# DC26_HHV_challenge.net
KiCad netlist of a schematic drawn in EAGLE
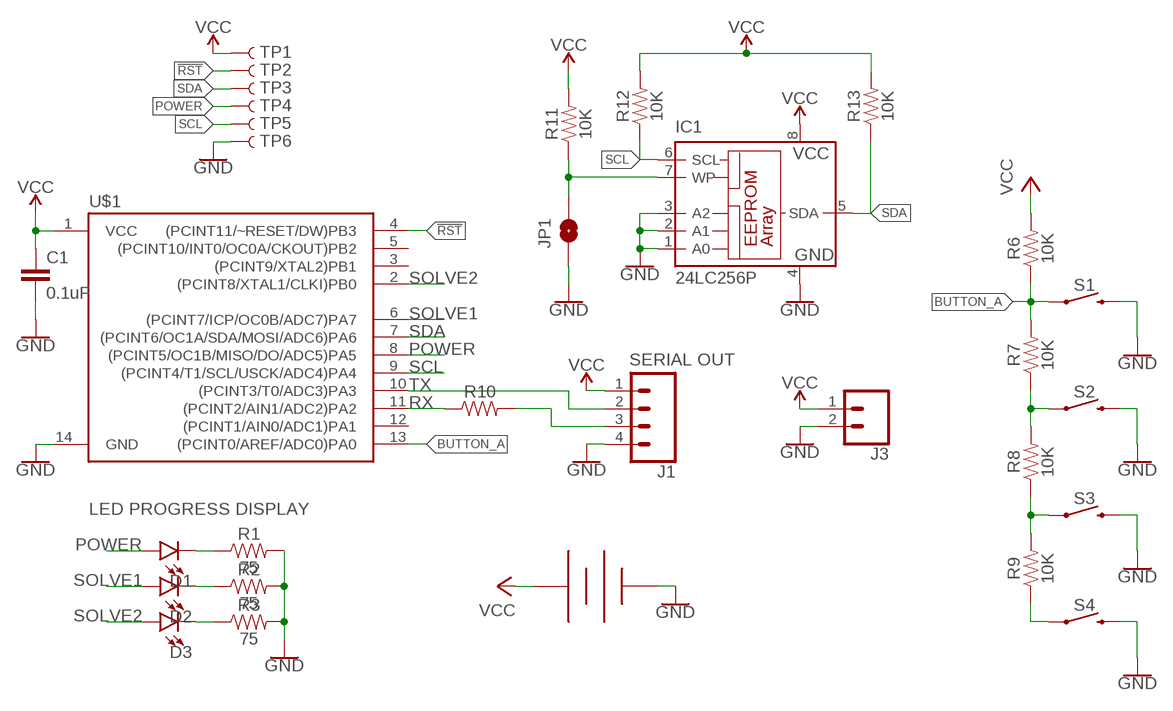
[diagram p0: schematic, sheet 1]

(export (version "E")
  (design (tool "Eeschema 10.0.6"))
  (components
    (comp (ref "BT1")
      (value "BAT-HLD-001-THM")
      (footprint "eagle-import:BAT-HLD-001-THM")
      (libsource (lib "eagle-import") (part "BAT-HLD-001-THM"))
    )
    (comp (ref "C1")
      (value "0.1uF")
      (footprint "eagle-import:0603")
      (libsource (lib "eagle-import") (part "0.1UF-0603-25V-(+80/-20%)"))
    )
    (comp (ref "D1")
      (value "LED5MM")
      (footprint "eagle-import:LED_5MM")
      (libsource (lib "eagle-import") (part "LED5MM"))
    )
    (comp (ref "D2")
      (value "LED5MM")
      (footprint "eagle-import:LED_5MM")
      (libsource (lib "eagle-import") (part "LED5MM"))
    )
    (comp (ref "D3")
      (value "LED5MM")
      (footprint "eagle-import:LED_5MM")
      (libsource (lib "eagle-import") (part "LED5MM"))
    )
    (comp (ref "IC1")
      (value "24LC256P")
      (footprint "eagle-import:DIL8")
      (fields (field (name "MF") "MICROCHIP") (field (name "MPN") "24LC256-E/P"))
      (libsource (lib "eagle-import") (part "24PLC256"))
    )
    (comp (ref "J1")
      (value "CONN_04LOCK")
      (footprint "eagle-import:1X04_LOCK")
      (libsource (lib "eagle-import") (part "CONN_04LOCK"))
    )
    (comp (ref "J3")
      (value "CONN_02PTH3")
      (footprint "eagle-import:1X02_LONGPADS")
      (libsource (lib "eagle-import") (part "CONN_02PTH3"))
    )
    (comp (ref "JP1")
      (value "JUMPER-SMT_2_NO_SILK")
      (footprint "eagle-import:SMT-JUMPER_2_NO_SILK")
      (libsource (lib "eagle-import") (part "JUMPER-SMT_2_NO_SILK"))
    )
    (comp (ref "R1")
      (value "75")
      (footprint "eagle-import:0805")
      (libsource (lib "eagle-import") (part "RESISTOR0805"))
    )
    (comp (ref "R2")
      (value "75")
      (footprint "eagle-import:0805")
      (libsource (lib "eagle-import") (part "RESISTOR0805"))
    )
    (comp (ref "R3")
      (value "75")
      (footprint "eagle-import:0805")
      (libsource (lib "eagle-import") (part "RESISTOR0805"))
    )
    (comp (ref "R6")
      (value "10K")
      (footprint "eagle-import:AXIAL-0.3")
      (libsource (lib "eagle-import") (part "RESISTORAXIAL-0.3"))
    )
    (comp (ref "R7")
      (value "10K")
      (footprint "eagle-import:AXIAL-0.3")
      (libsource (lib "eagle-import") (part "RESISTORAXIAL-0.3"))
    )
    (comp (ref "R8")
      (value "10K")
      (footprint "eagle-import:AXIAL-0.3")
      (libsource (lib "eagle-import") (part "RESISTORAXIAL-0.3"))
    )
    (comp (ref "R9")
      (value "10K")
      (footprint "eagle-import:AXIAL-0.3")
      (libsource (lib "eagle-import") (part "RESISTORAXIAL-0.3"))
    )
    (comp (ref "R10")
      (value "RESISTOR0805")
      (footprint "eagle-import:0805")
      (libsource (lib "eagle-import") (part "RESISTOR0805"))
    )
    (comp (ref "R11")
      (value "10K")
      (footprint "eagle-import:AXIAL-0.3")
      (libsource (lib "eagle-import") (part "RESISTORAXIAL-0.3"))
    )
    (comp (ref "R12")
      (value "10K")
      (footprint "eagle-import:AXIAL-0.3")
      (libsource (lib "eagle-import") (part "RESISTORAXIAL-0.3"))
    )
    (comp (ref "R13")
      (value "10K")
      (footprint "eagle-import:AXIAL-0.3")
      (libsource (lib "eagle-import") (part "RESISTORAXIAL-0.3"))
    )
    (comp (ref "S1")
      (value "MOMENTARY-SWITCH-SPST-PTH-6.0MM")
      (footprint "eagle-import:TACTILE_SWITCH_PTH_6.0MM")
      (libsource (lib "eagle-import") (part "MOMENTARY-SWITCH-SPST-PTH-6.0MM"))
    )
    (comp (ref "S2")
      (value "MOMENTARY-SWITCH-SPST-PTH-6.0MM")
      (footprint "eagle-import:TACTILE_SWITCH_PTH_6.0MM")
      (libsource (lib "eagle-import") (part "MOMENTARY-SWITCH-SPST-PTH-6.0MM"))
    )
    (comp (ref "S3")
      (value "MOMENTARY-SWITCH-SPST-PTH-6.0MM")
      (footprint "eagle-import:TACTILE_SWITCH_PTH_6.0MM")
      (libsource (lib "eagle-import") (part "MOMENTARY-SWITCH-SPST-PTH-6.0MM"))
    )
    (comp (ref "S4")
      (value "MOMENTARY-SWITCH-SPST-PTH-6.0MM")
      (footprint "eagle-import:TACTILE_SWITCH_PTH_6.0MM")
      (libsource (lib "eagle-import") (part "MOMENTARY-SWITCH-SPST-PTH-6.0MM"))
    )
    (comp (ref "TP1")
      (value "TEST-POINT3X4")
      (footprint "eagle-import:PAD.03X.04")
      (libsource (lib "eagle-import") (part "TEST-POINT3X4"))
    )
    (comp (ref "TP2")
      (value "TEST-POINT3X4")
      (footprint "eagle-import:PAD.03X.04")
      (libsource (lib "eagle-import") (part "TEST-POINT3X4"))
    )
    (comp (ref "TP3")
      (value "TEST-POINT3X4")
      (footprint "eagle-import:PAD.03X.04")
      (libsource (lib "eagle-import") (part "TEST-POINT3X4"))
    )
    (comp (ref "TP4")
      (value "TEST-POINT3X4")
      (footprint "eagle-import:PAD.03X.04")
      (libsource (lib "eagle-import") (part "TEST-POINT3X4"))
    )
    (comp (ref "TP5")
      (value "TEST-POINT3X4")
      (footprint "eagle-import:PAD.03X.04")
      (libsource (lib "eagle-import") (part "TEST-POINT3X4"))
    )
    (comp (ref "TP6")
      (value "TEST-POINT3X4")
      (footprint "eagle-import:PAD.03X.04")
      (libsource (lib "eagle-import") (part "TEST-POINT3X4"))
    )
    (comp (ref "U$1")
      (value "ATTINY84ATTINY84-20PU")
      (footprint "eagle-import:DIP14")
      (libsource (lib "eagle-import") (part "ATTINY84ATTINY84-20PU"))
    )
  )
  (nets
    (net (code "1") (name "/RX") (class "Default")
      (node (ref "J1") (pin "3") (pinfunction "3_3") (pintype "passive"))
      (node (ref "R10") (pin "2") (pinfunction "2_2") (pintype "passive"))
    )
    (net (code "2") (name "/SOLVE1") (class "Default")
      (node (ref "D2") (pin "A") (pinfunction "A_A") (pintype "passive"))
      (node (ref "U$1") (pin "6") (pinfunction "(PCINT7/ICP/OC0B/ADC7)PA7_6") (pintype "bidirectional"))
    )
    (net (code "3") (name "/SOLVE2") (class "Default")
      (node (ref "D3") (pin "A") (pinfunction "A_A") (pintype "passive"))
      (node (ref "U$1") (pin "2") (pinfunction "(PCINT8/XTAL1/CLKI)PB0_2") (pintype "bidirectional"))
    )
    (net (code "4") (name "/TX") (class "Default")
      (node (ref "J1") (pin "2") (pinfunction "2_2") (pintype "passive"))
      (node (ref "U$1") (pin "10") (pinfunction "(PCINT3/T0/ADC3)PA3_10") (pintype "bidirectional"))
    )
    (net (code "5") (name "/~{RST}") (class "Default")
      (node (ref "TP2") (pin "P$1") (pinfunction "1_P$1") (pintype "bidirectional"))
      (node (ref "U$1") (pin "4") (pinfunction "(PCINT11/~{RESET/DW})PB3_4") (pintype "bidirectional"))
    )
    (net (code "6") (name "BUTTON_A") (class "Default")
      (node (ref "R6") (pin "P$1") (pinfunction "1_P$1") (pintype "passive"))
      (node (ref "R7") (pin "P$2") (pinfunction "2_P$2") (pintype "passive"))
      (node (ref "S1") (pin "1") (pinfunction "1_1") (pintype "passive"))
      (node (ref "U$1") (pin "13") (pinfunction "(PCINT0/AREF/ADC0)PA0_13") (pintype "bidirectional"))
    )
    (net (code "7") (name "GND") (class "Default")
      (node (ref "BT1") (pin "-") (pinfunction "VSS_-") (pintype "bidirectional"))
      (node (ref "C1") (pin "2") (pinfunction "2_2") (pintype "passive"))
      (node (ref "IC1") (pin "1") (pinfunction "A0_1") (pintype "input"))
      (node (ref "IC1") (pin "2") (pinfunction "A1_2") (pintype "input"))
      (node (ref "IC1") (pin "3") (pinfunction "A2_3") (pintype "input"))
      (node (ref "IC1") (pin "4") (pinfunction "GND_4") (pintype "power_in"))
      (node (ref "J1") (pin "4") (pinfunction "4_4") (pintype "passive"))
      (node (ref "J3") (pin "2") (pinfunction "2_2") (pintype "passive"))
      (node (ref "JP1") (pin "1") (pinfunction "1_1") (pintype "passive"))
      (node (ref "R1") (pin "2") (pinfunction "2_2") (pintype "passive"))
      (node (ref "R2") (pin "2") (pinfunction "2_2") (pintype "passive"))
      (node (ref "R3") (pin "2") (pinfunction "2_2") (pintype "passive"))
      (node (ref "S1") (pin "3") (pinfunction "2_3") (pintype "passive"))
      (node (ref "S2") (pin "3") (pinfunction "2_3") (pintype "passive"))
      (node (ref "S3") (pin "3") (pinfunction "2_3") (pintype "passive"))
      (node (ref "S4") (pin "3") (pinfunction "2_3") (pintype "passive"))
      (node (ref "TP6") (pin "P$1") (pinfunction "1_P$1") (pintype "bidirectional"))
      (node (ref "U$1") (pin "14") (pinfunction "GND_14") (pintype "bidirectional"))
    )
    (net (code "8") (name "Net-(D1-C)") (class "Default")
      (node (ref "D1") (pin "K") (pinfunction "C_K") (pintype "passive"))
      (node (ref "R1") (pin "1") (pinfunction "1_1") (pintype "passive"))
    )
    (net (code "9") (name "Net-(D2-C)") (class "Default")
      (node (ref "D2") (pin "K") (pinfunction "C_K") (pintype "passive"))
      (node (ref "R2") (pin "1") (pinfunction "1_1") (pintype "passive"))
    )
    (net (code "10") (name "Net-(D3-C)") (class "Default")
      (node (ref "D3") (pin "K") (pinfunction "C_K") (pintype "passive"))
      (node (ref "R3") (pin "1") (pinfunction "1_1") (pintype "passive"))
    )
    (net (code "11") (name "Net-(IC1-WP)") (class "Default")
      (node (ref "IC1") (pin "7") (pinfunction "WP_7") (pintype "input"))
      (node (ref "JP1") (pin "2") (pinfunction "2_2") (pintype "passive"))
      (node (ref "R11") (pin "P$1") (pinfunction "1_P$1") (pintype "passive"))
    )
    (net (code "12") (name "Net-(R7-1)") (class "Default")
      (node (ref "R7") (pin "P$1") (pinfunction "1_P$1") (pintype "passive"))
      (node (ref "R8") (pin "P$2") (pinfunction "2_P$2") (pintype "passive"))
      (node (ref "S2") (pin "1") (pinfunction "1_1") (pintype "passive"))
    )
    (net (code "13") (name "Net-(R8-1)") (class "Default")
      (node (ref "R8") (pin "P$1") (pinfunction "1_P$1") (pintype "passive"))
      (node (ref "R9") (pin "P$2") (pinfunction "2_P$2") (pintype "passive"))
      (node (ref "S3") (pin "1") (pinfunction "1_1") (pintype "passive"))
    )
    (net (code "14") (name "Net-(R9-1)") (class "Default")
      (node (ref "R9") (pin "P$1") (pinfunction "1_P$1") (pintype "passive"))
      (node (ref "S4") (pin "1") (pinfunction "1_1") (pintype "passive"))
    )
    (net (code "15") (name "Net-(U$1-(PCINT2{slash}AIN1{slash}ADC2)PA2)") (class "Default")
      (node (ref "R10") (pin "1") (pinfunction "1_1") (pintype "passive"))
      (node (ref "U$1") (pin "11") (pinfunction "(PCINT2/AIN1/ADC2)PA2_11") (pintype "bidirectional"))
    )
    (net (code "16") (name "POWER") (class "Default")
      (node (ref "D1") (pin "A") (pinfunction "A_A") (pintype "passive"))
      (node (ref "TP4") (pin "P$1") (pinfunction "1_P$1") (pintype "bidirectional"))
      (node (ref "U$1") (pin "8") (pinfunction "(PCINT5/OC1B/MISO/DO/ADC5)PA5_8") (pintype "bidirectional"))
    )
    (net (code "17") (name "SCL") (class "Default")
      (node (ref "IC1") (pin "6") (pinfunction "SCL_6") (pintype "input"))
      (node (ref "R12") (pin "P$1") (pinfunction "1_P$1") (pintype "passive"))
      (node (ref "TP5") (pin "P$1") (pinfunction "1_P$1") (pintype "bidirectional"))
      (node (ref "U$1") (pin "9") (pinfunction "(PCINT4/T1/SCL/USCK/ADC4)PA4_9") (pintype "bidirectional"))
    )
    (net (code "18") (name "SDA") (class "Default")
      (node (ref "IC1") (pin "5") (pinfunction "SDA_5") (pintype "bidirectional"))
      (node (ref "R13") (pin "P$1") (pinfunction "1_P$1") (pintype "passive"))
      (node (ref "TP3") (pin "P$1") (pinfunction "1_P$1") (pintype "bidirectional"))
      (node (ref "U$1") (pin "7") (pinfunction "(PCINT6/OC1A/SDA/MOSI/ADC6)PA6_7") (pintype "bidirectional"))
    )
    (net (code "19") (name "VCC") (class "Default")
      (node (ref "BT1") (pin "+@0") (pinfunction "VCC_+@0") (pintype "bidirectional"))
      (node (ref "BT1") (pin "+@1") (pinfunction "VCC_+@1") (pintype "bidirectional"))
      (node (ref "BT1") (pin "+@2") (pinfunction "VCC_+@2") (pintype "bidirectional"))
      (node (ref "BT1") (pin "+@3") (pinfunction "VCC_+@3") (pintype "bidirectional"))
      (node (ref "C1") (pin "1") (pinfunction "1_1") (pintype "passive"))
      (node (ref "IC1") (pin "8") (pinfunction "VCC_8") (pintype "power_in"))
      (node (ref "J1") (pin "1") (pinfunction "1_1") (pintype "passive"))
      (node (ref "J3") (pin "1") (pinfunction "1_1") (pintype "passive"))
      (node (ref "R11") (pin "P$2") (pinfunction "2_P$2") (pintype "passive"))
      (node (ref "R12") (pin "P$2") (pinfunction "2_P$2") (pintype "passive"))
      (node (ref "R13") (pin "P$2") (pinfunction "2_P$2") (pintype "passive"))
      (node (ref "R6") (pin "P$2") (pinfunction "2_P$2") (pintype "passive"))
      (node (ref "TP1") (pin "P$1") (pinfunction "1_P$1") (pintype "bidirectional"))
      (node (ref "U$1") (pin "1") (pinfunction "VCC_1") (pintype "bidirectional"))
    )
    (net (code "20") (name "unconnected-(U$1-(PCINT1{slash}AIN0{slash}ADC1)PA1-Pad12)") (class "Default")
      (node (ref "U$1") (pin "12") (pinfunction "(PCINT1/AIN0/ADC1)PA1_12") (pintype "bidirectional"))
    )
    (net (code "21") (name "unconnected-(U$1-(PCINT9{slash}XTAL2)PB1-Pad3)") (class "Default")
      (node (ref "U$1") (pin "3") (pinfunction "(PCINT9/XTAL2)PB1_3") (pintype "bidirectional"))
    )
    (net (code "22") (name "unconnected-(U$1-(PCINT10{slash}INT0{slash}OC0A{slash}CKOUT)PB2-Pad5)") (class "Default")
      (node (ref "U$1") (pin "5") (pinfunction "(PCINT10/INT0/OC0A/CKOUT)PB2_5") (pintype "bidirectional"))
    )
  )
)
